# Light_SOT32_bottom.net
KiCad netlist of a schematic drawn in EAGLE
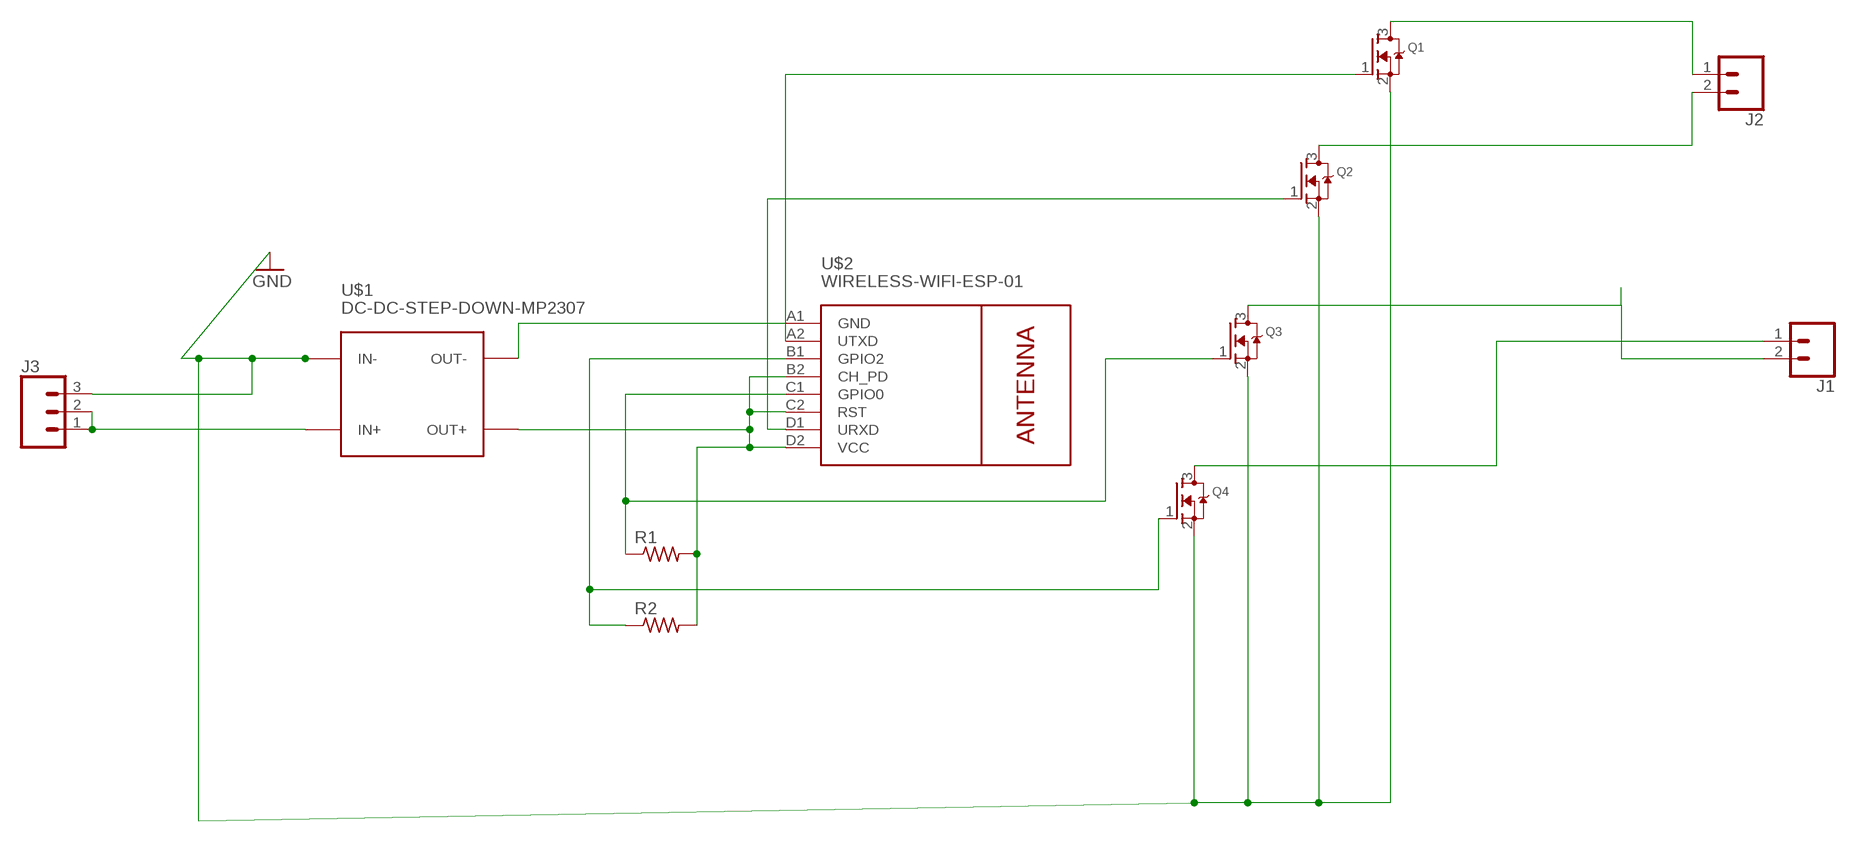
[diagram p0: schematic, sheet 1]

(export (version "E")
  (design (tool "Eeschema 10.0.6"))
  (components
    (comp (ref "J1")
      (value "CONN_023.5MM")
      (footprint "eagle-import:SCREWTERMINAL-3.5MM-2")
      (libsource (lib "eagle-import") (part "CONN_023.5MM"))
    )
    (comp (ref "J2")
      (value "CONN_023.5MM")
      (footprint "eagle-import:SCREWTERMINAL-3.5MM-2")
      (libsource (lib "eagle-import") (part "CONN_023.5MM"))
    )
    (comp (ref "J3")
      (value "CONN_03SCREW")
      (footprint "eagle-import:SCREWTERMINAL-3.5MM-3")
      (libsource (lib "eagle-import") (part "CONN_03SCREW"))
    )
    (comp (ref "Q1")
      (value "MOSFET-NREFLOW")
      (footprint "eagle-import:SOT23")
      (libsource (lib "eagle-import") (part "MOSFET-NREFLOW"))
    )
    (comp (ref "Q2")
      (value "MOSFET-NREFLOW")
      (footprint "eagle-import:SOT23")
      (libsource (lib "eagle-import") (part "MOSFET-NREFLOW"))
    )
    (comp (ref "Q3")
      (value "MOSFET-NREFLOW")
      (footprint "eagle-import:SOT23")
      (libsource (lib "eagle-import") (part "MOSFET-NREFLOW"))
    )
    (comp (ref "Q4")
      (value "MOSFET-NREFLOW")
      (footprint "eagle-import:SOT23")
      (libsource (lib "eagle-import") (part "MOSFET-NREFLOW"))
    )
    (comp (ref "R1")
      (value "R-US_R0805")
      (footprint "eagle-import:R0805")
      (libsource (lib "eagle-import") (part "R-US_R0805"))
    )
    (comp (ref "R2")
      (value "R-US_R0805")
      (footprint "eagle-import:R0805")
      (libsource (lib "eagle-import") (part "R-US_R0805"))
    )
    (comp (ref "U$1")
      (value "DC-DC-STEP-DOWN-MP2307")
      (footprint "eagle-import:DC-DC-STEP-DOWN-MP2307")
      (libsource (lib "eagle-import") (part "DC-DC-STEP-DOWN-MP2307"))
    )
    (comp (ref "U$2")
      (value "WIRELESS-WIFI-ESP-01")
      (footprint "eagle-import:WIRELESS-WIFI-ESP-01")
      (fields (field (name "SPICEPREFIX") "X"))
      (libsource (lib "eagle-import") (part "WIRELESS-WIFI-ESP-01"))
    )
  )
  (nets
    (net (code "1") (name "GND") (class "Default")
      (node (ref "J3") (pin "3") (pinfunction "3_3") (pintype "passive"))
      (node (ref "Q1") (pin "2") (pinfunction "S_2") (pintype "bidirectional"))
      (node (ref "Q2") (pin "2") (pinfunction "S_2") (pintype "bidirectional"))
      (node (ref "Q3") (pin "2") (pinfunction "S_2") (pintype "bidirectional"))
      (node (ref "Q4") (pin "2") (pinfunction "S_2") (pintype "bidirectional"))
      (node (ref "U$1") (pin "IN-") (pinfunction "IN-_IN-") (pintype "bidirectional"))
    )
    (net (code "2") (name "Net-(J3-Pad1)") (class "Default")
      (node (ref "J3") (pin "1") (pinfunction "1_1") (pintype "passive"))
      (node (ref "J3") (pin "2") (pinfunction "2_2") (pintype "passive"))
      (node (ref "U$1") (pin "IN+") (pinfunction "IN+_IN+") (pintype "bidirectional"))
    )
    (net (code "3") (name "Net-(Q1-D)") (class "Default")
      (node (ref "J2") (pin "1") (pinfunction "1_1") (pintype "passive"))
      (node (ref "Q1") (pin "3") (pinfunction "D_3") (pintype "bidirectional"))
    )
    (net (code "4") (name "Net-(Q1-G)") (class "Default")
      (node (ref "Q1") (pin "1") (pinfunction "G_1") (pintype "bidirectional"))
      (node (ref "U$2") (pin "A2") (pinfunction "UTXD_A2") (pintype "bidirectional"))
    )
    (net (code "5") (name "Net-(Q2-D)") (class "Default")
      (node (ref "J2") (pin "2") (pinfunction "2_2") (pintype "passive"))
      (node (ref "Q2") (pin "3") (pinfunction "D_3") (pintype "bidirectional"))
    )
    (net (code "6") (name "Net-(Q2-G)") (class "Default")
      (node (ref "Q2") (pin "1") (pinfunction "G_1") (pintype "bidirectional"))
      (node (ref "U$2") (pin "D1") (pinfunction "URXD_D1") (pintype "bidirectional"))
    )
    (net (code "7") (name "Net-(Q3-D)") (class "Default")
      (node (ref "J1") (pin "2") (pinfunction "2_2") (pintype "passive"))
      (node (ref "Q3") (pin "3") (pinfunction "D_3") (pintype "bidirectional"))
    )
    (net (code "8") (name "Net-(Q3-G)") (class "Default")
      (node (ref "Q3") (pin "1") (pinfunction "G_1") (pintype "bidirectional"))
      (node (ref "R1") (pin "1") (pinfunction "1_1") (pintype "passive"))
      (node (ref "U$2") (pin "C1") (pinfunction "GPIO0_C1") (pintype "bidirectional"))
    )
    (net (code "9") (name "Net-(Q4-D)") (class "Default")
      (node (ref "J1") (pin "1") (pinfunction "1_1") (pintype "passive"))
      (node (ref "Q4") (pin "3") (pinfunction "D_3") (pintype "bidirectional"))
    )
    (net (code "10") (name "Net-(Q4-G)") (class "Default")
      (node (ref "Q4") (pin "1") (pinfunction "G_1") (pintype "bidirectional"))
      (node (ref "R2") (pin "1") (pinfunction "1_1") (pintype "passive"))
      (node (ref "U$2") (pin "B1") (pinfunction "GPIO2_B1") (pintype "bidirectional"))
    )
    (net (code "11") (name "Net-(U$2-CH_PD)") (class "Default")
      (node (ref "R1") (pin "2") (pinfunction "2_2") (pintype "passive"))
      (node (ref "R2") (pin "2") (pinfunction "2_2") (pintype "passive"))
      (node (ref "U$1") (pin "OUT+") (pinfunction "OUT+_OUT+") (pintype "bidirectional"))
      (node (ref "U$2") (pin "B2") (pinfunction "CH_PD_B2") (pintype "bidirectional"))
      (node (ref "U$2") (pin "C2") (pinfunction "RST_C2") (pintype "bidirectional"))
      (node (ref "U$2") (pin "D2") (pinfunction "VCC_D2") (pintype "power_in"))
    )
    (net (code "12") (name "Net-(U$2-GND)") (class "Default")
      (node (ref "U$1") (pin "OUT-") (pinfunction "OUT-_OUT-") (pintype "bidirectional"))
      (node (ref "U$2") (pin "A1") (pinfunction "GND_A1") (pintype "power_in"))
    )
  )
)
